# 1010829PA_HVFlyback_GD_Testboard_Flyback.net
KiCad netlist of a schematic drawn in Altium Designer
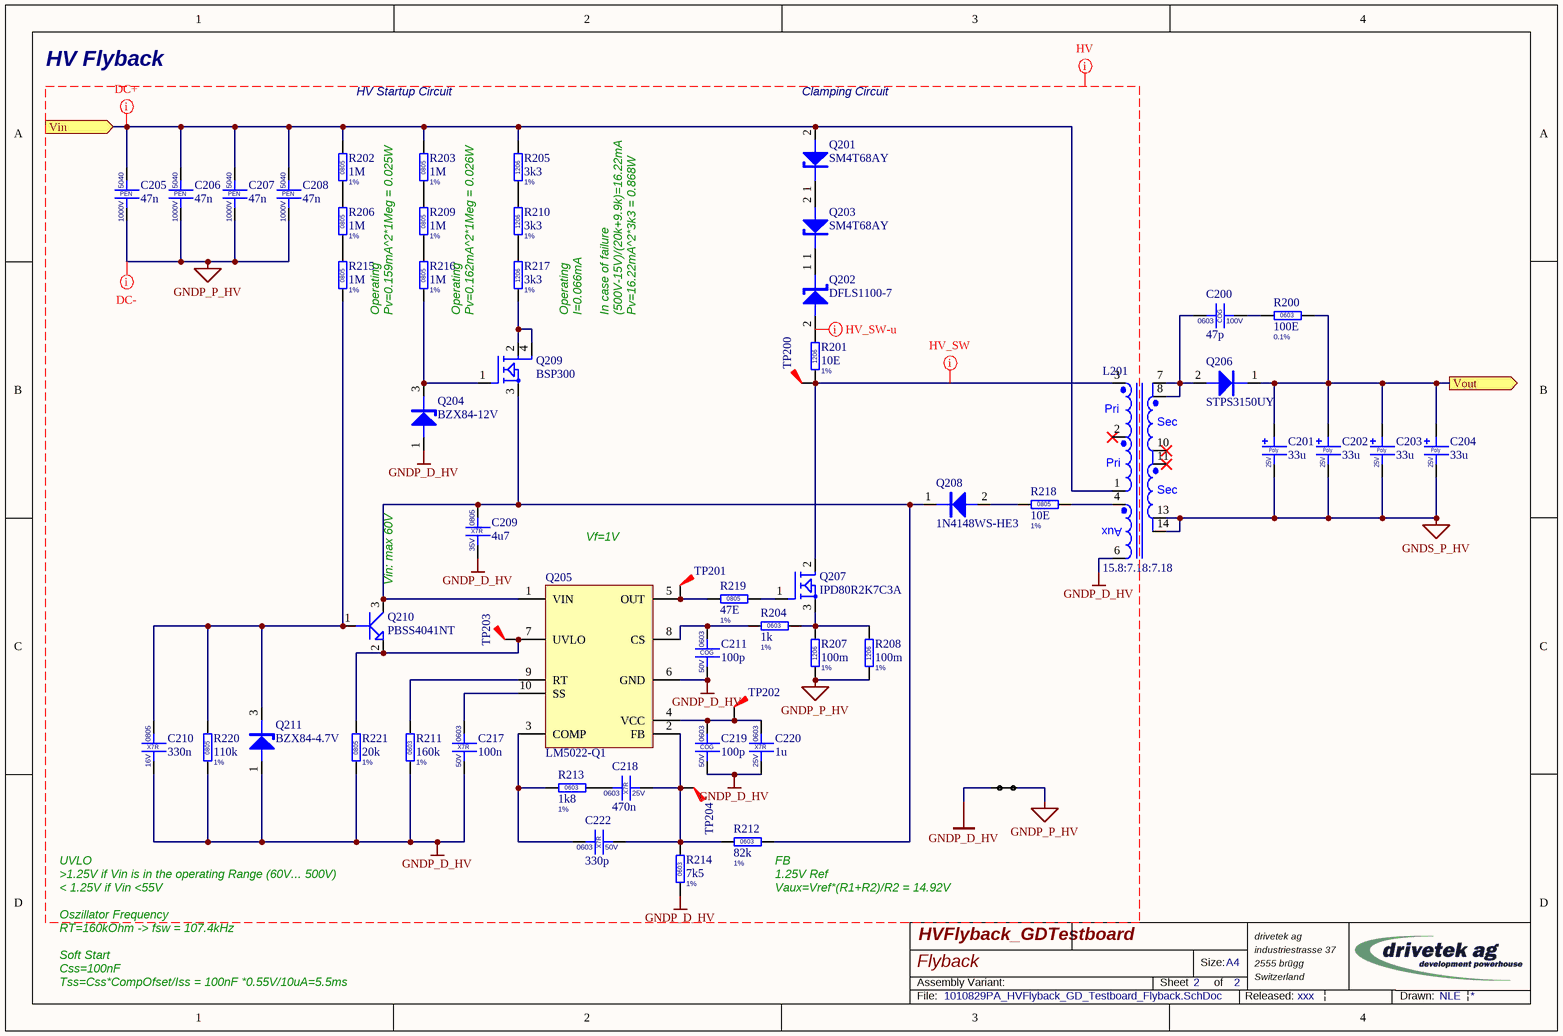
[diagram p0: 1010829PA_HVFlyback_GD_Testboard_Flyback.SchDoc]

(export (version "E")
  (design (tool "Eeschema 10.0.6"))
  (components
    (comp (ref "C200")
      (value "47p")
      (footprint "02_0603_DRK_1-7x1-0x0-9")
      (fields
        (field (name "CASENAME") "0603")
        (field (name "TYPE3") "COG")
        (field (name "VOLTAGE") "100V")
        (field (name "PART NUMBER") "02-0270")
        (field (name "TOLERANCE") "5")
        (field (name "AUTHOR") "RLE")
      )
      (libsource (lib "drivetek") (part "02_CAP"))
    )
    (comp (ref "C201")
      (value "33u")
      (footprint "02_ELKO-SMD-4x7-4_DRK_4-3x7-3x1-9")
      (fields
        (field (name "VOLTAGE") "25V")
        (field (name "TYPE2") "Poly")
        (field (name "PART NUMBER") "02-0399")
        (field (name "TOLERANCE") "20")
        (field (name "AUTHOR") "LME")
      )
      (libsource (lib "drivetek") (part "02_CAP-POL-P1-N2"))
    )
    (comp (ref "C202")
      (value "33u")
      (footprint "02_ELKO-SMD-4x7-4_DRK_4-3x7-3x1-9")
      (fields
        (field (name "VOLTAGE") "25V")
        (field (name "TYPE2") "Poly")
        (field (name "PART NUMBER") "02-0399")
        (field (name "TOLERANCE") "20")
        (field (name "AUTHOR") "LME")
      )
      (libsource (lib "drivetek") (part "02_CAP-POL-P1-N2"))
    )
    (comp (ref "C203")
      (value "33u")
      (footprint "02_ELKO-SMD-4x7-4_DRK_4-3x7-3x1-9")
      (fields
        (field (name "VOLTAGE") "25V")
        (field (name "TYPE2") "Poly")
        (field (name "PART NUMBER") "02-0399")
        (field (name "TOLERANCE") "20")
        (field (name "AUTHOR") "LME")
      )
      (libsource (lib "drivetek") (part "02_CAP-POL-P1-N2"))
    )
    (comp (ref "C204")
      (value "33u")
      (footprint "02_ELKO-SMD-4x7-4_DRK_4-3x7-3x1-9")
      (fields
        (field (name "VOLTAGE") "25V")
        (field (name "TYPE2") "Poly")
        (field (name "PART NUMBER") "02-0399")
        (field (name "TOLERANCE") "20")
        (field (name "AUTHOR") "LME")
      )
      (libsource (lib "drivetek") (part "02_CAP-POL-P1-N2"))
    )
    (comp (ref "C205")
      (value "47n")
      (footprint "02_5040_DRK_3-5mm")
      (fields
        (field (name "CASENAME") "5040")
        (field (name "TYPE3") "PEN")
        (field (name "VOLTAGE") "1000V")
        (field (name "PART NUMBER") "02-0364")
        (field (name "TOLERANCE") "10")
        (field (name "AUTHOR") "IKU")
      )
      (libsource (lib "drivetek") (part "02_CAP"))
    )
    (comp (ref "C206")
      (value "47n")
      (footprint "02_5040_DRK_3-5mm")
      (fields
        (field (name "CASENAME") "5040")
        (field (name "TYPE3") "PEN")
        (field (name "VOLTAGE") "1000V")
        (field (name "PART NUMBER") "02-0364")
        (field (name "TOLERANCE") "10")
        (field (name "AUTHOR") "IKU")
      )
      (libsource (lib "drivetek") (part "02_CAP"))
    )
    (comp (ref "C207")
      (value "47n")
      (footprint "02_5040_DRK_3-5mm")
      (fields
        (field (name "CASENAME") "5040")
        (field (name "TYPE3") "PEN")
        (field (name "VOLTAGE") "1000V")
        (field (name "PART NUMBER") "02-0364")
        (field (name "TOLERANCE") "10")
        (field (name "AUTHOR") "IKU")
      )
      (libsource (lib "drivetek") (part "02_CAP"))
    )
    (comp (ref "C208")
      (value "47n")
      (footprint "02_5040_DRK_3-5mm")
      (fields
        (field (name "CASENAME") "5040")
        (field (name "TYPE3") "PEN")
        (field (name "VOLTAGE") "1000V")
        (field (name "PART NUMBER") "02-0364")
        (field (name "TOLERANCE") "10")
        (field (name "AUTHOR") "IKU")
      )
      (libsource (lib "drivetek") (part "02_CAP"))
    )
    (comp (ref "C209")
      (value "4u7")
      (footprint "02_0805_DRK_2-2x1-5x1-3")
      (fields
        (field (name "CASENAME") "0805")
        (field (name "TYPE3") "X7R")
        (field (name "VOLTAGE") "35V")
        (field (name "PART NUMBER") "02-0353")
        (field (name "TOLERANCE") "10")
        (field (name "AUTHOR") "RLE")
      )
      (libsource (lib "drivetek") (part "02_CAP"))
    )
    (comp (ref "C210")
      (value "330n")
      (footprint "02_0805_DRK_2-2x1-5x1-3")
      (fields
        (field (name "CASENAME") "0805")
        (field (name "TYPE3") "X7R")
        (field (name "VOLTAGE") "16V")
        (field (name "PART NUMBER") "02-0058")
        (field (name "TOLERANCE") "10")
        (field (name "AUTHOR") "CBA")
        (field (name "CHECKED") "HHU")
      )
      (libsource (lib "drivetek") (part "02_CAP"))
    )
    (comp (ref "C211")
      (value "100p")
      (footprint "02_0603_DRK_1-7x1-0x0-9")
      (fields
        (field (name "CASENAME") "0603")
        (field (name "TYPE3") "COG")
        (field (name "VOLTAGE") "50V")
        (field (name "PART NUMBER") "02-0380")
        (field (name "TOLERANCE") "5")
        (field (name "AUTHOR") "RLE")
      )
      (libsource (lib "drivetek") (part "02_CAP"))
    )
    (comp (ref "C217")
      (value "100n")
      (footprint "02_0603_DRK_1-7x1-0x0-9")
      (fields
        (field (name "CASENAME") "0603")
        (field (name "TYPE3") "X7R")
        (field (name "VOLTAGE") "50V")
        (field (name "PART NUMBER") "02-0184")
        (field (name "TOLERANCE") "10")
        (field (name "AUTHOR") "MSC")
        (field (name "CHECKED") "HHU")
      )
      (libsource (lib "drivetek") (part "02_CAP"))
    )
    (comp (ref "C218")
      (value "470n")
      (footprint "02_0603_DRK_1-7x1-0x0-9")
      (fields
        (field (name "CASENAME") "0603")
        (field (name "TYPE3") "X7R")
        (field (name "VOLTAGE") "25V")
        (field (name "PART NUMBER") "02-0206")
        (field (name "TOLERANCE") "10")
        (field (name "AUTHOR") "RLE")
        (field (name "CHECKED") "CRA")
      )
      (libsource (lib "drivetek") (part "02_CAP"))
    )
    (comp (ref "C219")
      (value "100p")
      (footprint "02_0603_DRK_1-7x1-0x0-9")
      (fields
        (field (name "CASENAME") "0603")
        (field (name "TYPE3") "COG")
        (field (name "VOLTAGE") "50V")
        (field (name "PART NUMBER") "02-0380")
        (field (name "TOLERANCE") "5")
        (field (name "AUTHOR") "RLE")
      )
      (libsource (lib "drivetek") (part "02_CAP"))
    )
    (comp (ref "C220")
      (value "1u")
      (footprint "02_0603_DRK_1-7x1-0x0-9")
      (fields
        (field (name "CASENAME") "0603")
        (field (name "TYPE3") "X7R")
        (field (name "VOLTAGE") "25V")
        (field (name "PART NUMBER") "02-0275")
        (field (name "TOLERANCE") "10")
        (field (name "AUTHOR") "SSC")
      )
      (libsource (lib "drivetek") (part "02_CAP"))
    )
    (comp (ref "C222")
      (value "330p")
      (footprint "02_0603_DRK_1-7x1-0x0-9")
      (fields
        (field (name "CASENAME") "0603")
        (field (name "TYPE3") "X7R")
        (field (name "VOLTAGE") "50V")
        (field (name "PART NUMBER") "02-0026")
        (field (name "TOLERANCE") "10")
        (field (name "AUTHOR") "CBA")
        (field (name "CHECKED") "HHU")
      )
      (libsource (lib "drivetek") (part "02_CAP"))
    )
    (comp (ref "J200")
      (value "3x1top")
      (footprint "12_NetCon_top_3x1")
      (description "NetCon")
      (fields (field (name "PART NUMBER") "12-0017") (field (name "AUTHOR") "MSC"))
      (libsource (lib "drivetek") (part "12_NetCon"))
    )
    (comp (ref "L201")
      (value "15.8:7.18:7.18")
      (footprint "06_TRA_DRK_WUERTH-750871630")
      (description "Flyback Transformer on Würth 070-6258 Bobbin")
      (fields (field (name "PART NUMBER") "06-0145") (field (name "AUTHOR") "NLE"))
      (libsource (lib "drivetek") (part "06_TRA_DRK_WUERTH-750871630"))
    )
    (comp (ref "Q201")
      (value "SM4T68AY")
      (footprint "03_SMA_DRK")
      (fields
        (field (name "PART NUMBER") "03-0427")
        (field (name "VOLTAGE") "58V")
        (field (name "AUTHOR") "NLE")
      )
      (libsource (lib "drivetek") (part "03_ZDIODE_A2-K1"))
    )
    (comp (ref "Q202")
      (value "DFLS1100-7")
      (footprint "03_POWERDI_DRK")
      (fields
        (field (name "PART NUMBER") "03-0225")
        (field (name "VOLTAGE") "100V")
        (field (name "AUTHOR") "CSI")
      )
      (libsource (lib "drivetek") (part "03_SCHOTTKY_A2-K1"))
    )
    (comp (ref "Q203")
      (value "SM4T68AY")
      (footprint "03_SMA_DRK")
      (fields
        (field (name "PART NUMBER") "03-0427")
        (field (name "VOLTAGE") "58V")
        (field (name "AUTHOR") "NLE")
      )
      (libsource (lib "drivetek") (part "03_ZDIODE_A2-K1"))
    )
    (comp (ref "Q204")
      (value "BZX84-12V")
      (footprint "03_SOT23_DRK")
      (fields (field (name "PART NUMBER") "03-0210") (field (name "VOLTAGE") "12V"))
      (libsource (lib "drivetek") (part "03_ZDIODE_A1-K3"))
    )
    (comp (ref "Q205")
      (value "LM5022-Q1")
      (footprint "04_VSSOP-10_DRK")
      (fields (field (name "PART NUMBER") "04-0502") (field (name "AUTHOR") "LME"))
      (libsource (lib "drivetek") (part "04_SPREG_LM5022"))
    )
    (comp (ref "Q206")
      (value "STPS3150UY")
      (footprint "03_SMB_DRK")
      (fields
        (field (name "PART NUMBER") "03-0428")
        (field (name "VOLTAGE") "150V")
        (field (name "AUTHOR") "NLE")
      )
      (libsource (lib "drivetek") (part "03_DIODE_A2-K1"))
    )
    (comp (ref "Q207")
      (value "IPD80R2K7C3A")
      (footprint "03_PG-TO252-3-11")
      (fields
        (field (name "PART NUMBER") "03-0426")
        (field (name "VOLTAGE") "800V")
        (field (name "AUTHOR") "NLE")
      )
      (libsource (lib "drivetek") (part "03_NMOS_G1-D2-S3"))
    )
    (comp (ref "Q208")
      (value "1N4148WS-HE3")
      (footprint "03_SOD323_DRK")
      (fields
        (field (name "PART NUMBER") "03-0429")
        (field (name "VOLTAGE") "100V")
        (field (name "AUTHOR") "NLE")
      )
      (libsource (lib "drivetek") (part "03_DIODE_A2-K1"))
    )
    (comp (ref "Q209")
      (value "BSP300")
      (footprint "03_SOT-223_DRK")
      (fields
        (field (name "PART NUMBER") "03-0432")
        (field (name "VOLTAGE") "800V")
        (field (name "AUTHOR") "NLE")
      )
      (libsource (lib "drivetek") (part "03_NMOS_G1-D2-S3-D4"))
    )
    (comp (ref "Q210")
      (value "PBSS4041NT")
      (footprint "03_SOT23_DRK")
      (fields
        (field (name "PART NUMBER") "03-0198")
        (field (name "VOLTAGE") "60V")
        (field (name "AUTHOR") "SSC")
      )
      (libsource (lib "drivetek") (part "03_NPN_1B-2E-3C"))
    )
    (comp (ref "Q211")
      (value "BZX84-4.7V")
      (footprint "03_SOT23_DRK")
      (fields
        (field (name "PART NUMBER") "03-0027")
        (field (name "VOLTAGE") "4V7")
        (field (name "AUTHOR") "CBA")
      )
      (libsource (lib "drivetek") (part "03_ZDIODE_A1-K3"))
    )
    (comp (ref "R200")
      (value "100E")
      (footprint "01_0603_DRK_1-7x1-0x0-55")
      (fields
        (field (name "TOLERANCE") "0.1%")
        (field (name "CASENAME") "0603")
        (field (name "PART NUMBER") "01-0584")
        (field (name "VOLTAGE") "75V")
        (field (name "POWER") "100m")
        (field (name "AUTHOR") "MFR")
      )
      (libsource (lib "drivetek") (part "01_RES"))
    )
    (comp (ref "R201")
      (value "10E")
      (footprint "01_1206_DRK_3-4x1-8x0-65")
      (fields
        (field (name "TOLERANCE") "1%")
        (field (name "CASENAME") "1206")
        (field (name "PART NUMBER") "01-0261")
        (field (name "VOLTAGE") "200V")
        (field (name "POWER") "125m")
        (field (name "AUTHOR") "CBA")
        (field (name "CHECKED") "CBA")
      )
      (libsource (lib "drivetek") (part "01_RES"))
    )
    (comp (ref "R202")
      (value "1M")
      (footprint "01_0805_DRK_2-2x1-5x0-65")
      (fields
        (field (name "TOLERANCE") "1%")
        (field (name "CASENAME") "0805")
        (field (name "PART NUMBER") "01-0158")
        (field (name "VOLTAGE") "150V")
        (field (name "POWER") "100m")
        (field (name "AUTHOR") "CBA")
        (field (name "CHECKED") "CBA")
      )
      (libsource (lib "drivetek") (part "01_RES"))
    )
    (comp (ref "R203")
      (value "1M")
      (footprint "01_0805_DRK_2-2x1-5x0-65")
      (fields
        (field (name "TOLERANCE") "1%")
        (field (name "CASENAME") "0805")
        (field (name "PART NUMBER") "01-0158")
        (field (name "VOLTAGE") "150V")
        (field (name "POWER") "100m")
        (field (name "AUTHOR") "CBA")
        (field (name "CHECKED") "CBA")
      )
      (libsource (lib "drivetek") (part "01_RES"))
    )
    (comp (ref "R204")
      (value "1k")
      (footprint "01_0603_DRK_1-7x1-0x0-55")
      (fields
        (field (name "TOLERANCE") "1%")
        (field (name "CASENAME") "0603")
        (field (name "PART NUMBER") "01-0003")
        (field (name "VOLTAGE") "50V")
        (field (name "POWER") "63m")
        (field (name "AUTHOR") "CBA")
        (field (name "CHECKED") "CBA")
      )
      (libsource (lib "drivetek") (part "01_RES"))
    )
    (comp (ref "R205")
      (value "3k3")
      (footprint "01_1206_DRK_3-4x1-8x0-65")
      (fields
        (field (name "TOLERANCE") "1%")
        (field (name "CASENAME") "1206")
        (field (name "PART NUMBER") "01-0317")
        (field (name "VOLTAGE") "200V")
        (field (name "POWER") "125m")
        (field (name "AUTHOR") "CBA")
        (field (name "CHECKED") "CBA")
      )
      (libsource (lib "drivetek") (part "01_RES"))
    )
    (comp (ref "R206")
      (value "1M")
      (footprint "01_0805_DRK_2-2x1-5x0-65")
      (fields
        (field (name "TOLERANCE") "1%")
        (field (name "CASENAME") "0805")
        (field (name "PART NUMBER") "01-0158")
        (field (name "VOLTAGE") "150V")
        (field (name "POWER") "100m")
        (field (name "AUTHOR") "CBA")
        (field (name "CHECKED") "CBA")
      )
      (libsource (lib "drivetek") (part "01_RES"))
    )
    (comp (ref "R207")
      (value "100m")
      (footprint "01_1206_DRK_3-4x1-8x0-65")
      (fields
        (field (name "TOLERANCE") "1%")
        (field (name "CASENAME") "1206")
        (field (name "PART NUMBER") "01-0780")
        (field (name "VOLTAGE") "200V")
        (field (name "POWER") "500m")
        (field (name "AUTHOR") "LME")
      )
      (libsource (lib "drivetek") (part "01_RES"))
    )
    (comp (ref "R208")
      (value "100m")
      (footprint "01_1206_DRK_3-4x1-8x0-65")
      (fields
        (field (name "TOLERANCE") "1%")
        (field (name "CASENAME") "1206")
        (field (name "PART NUMBER") "01-0780")
        (field (name "VOLTAGE") "200V")
        (field (name "POWER") "500m")
        (field (name "AUTHOR") "LME")
      )
      (libsource (lib "drivetek") (part "01_RES"))
    )
    (comp (ref "R209")
      (value "1M")
      (footprint "01_0805_DRK_2-2x1-5x0-65")
      (fields
        (field (name "TOLERANCE") "1%")
        (field (name "CASENAME") "0805")
        (field (name "PART NUMBER") "01-0158")
        (field (name "VOLTAGE") "150V")
        (field (name "POWER") "100m")
        (field (name "AUTHOR") "CBA")
        (field (name "CHECKED") "CBA")
      )
      (libsource (lib "drivetek") (part "01_RES"))
    )
    (comp (ref "R210")
      (value "3k3")
      (footprint "01_1206_DRK_3-4x1-8x0-65")
      (fields
        (field (name "TOLERANCE") "1%")
        (field (name "CASENAME") "1206")
        (field (name "PART NUMBER") "01-0317")
        (field (name "VOLTAGE") "200V")
        (field (name "POWER") "125m")
        (field (name "AUTHOR") "CBA")
        (field (name "CHECKED") "CBA")
      )
      (libsource (lib "drivetek") (part "01_RES"))
    )
    (comp (ref "R211")
      (value "160k")
      (footprint "01_0603_DRK_1-7x1-0x0-55")
      (fields
        (field (name "TOLERANCE") "1%")
        (field (name "CASENAME") "0603")
        (field (name "PART NUMBER") "01-0032")
        (field (name "VOLTAGE") "50V")
        (field (name "POWER") "63m")
        (field (name "AUTHOR") "CBA")
        (field (name "CHECKED") "CBA")
      )
      (libsource (lib "drivetek") (part "01_RES"))
    )
    (comp (ref "R212")
      (value "82k")
      (footprint "01_0603_DRK_1-7x1-0x0-55")
      (fields
        (field (name "TOLERANCE") "1%")
        (field (name "CASENAME") "0603")
        (field (name "PART NUMBER") "01-0120")
        (field (name "VOLTAGE") "50V")
        (field (name "POWER") "63m")
        (field (name "AUTHOR") "CBA")
        (field (name "CHECKED") "CBA")
      )
      (libsource (lib "drivetek") (part "01_RES"))
    )
    (comp (ref "R213")
      (value "1k8")
      (footprint "01_0603_DRK_1-7x1-0x0-55")
      (fields
        (field (name "TOLERANCE") "1%")
        (field (name "CASENAME") "0603")
        (field (name "PART NUMBER") "01-0035")
        (field (name "VOLTAGE") "50V")
        (field (name "POWER") "63m")
        (field (name "AUTHOR") "CBA")
        (field (name "CHECKED") "CBA")
      )
      (libsource (lib "drivetek") (part "01_RES"))
    )
    (comp (ref "R214")
      (value "7k5")
      (footprint "01_0603_DRK_1-7x1-0x0-55")
      (fields
        (field (name "TOLERANCE") "1%")
        (field (name "CASENAME") "0603")
        (field (name "PART NUMBER") "01-0114")
        (field (name "VOLTAGE") "50V")
        (field (name "POWER") "63m")
        (field (name "AUTHOR") "CBA")
        (field (name "CHECKED") "CBA")
      )
      (libsource (lib "drivetek") (part "01_RES"))
    )
    (comp (ref "R215")
      (value "1M")
      (footprint "01_0805_DRK_2-2x1-5x0-65")
      (fields
        (field (name "TOLERANCE") "1%")
        (field (name "CASENAME") "0805")
        (field (name "PART NUMBER") "01-0158")
        (field (name "VOLTAGE") "150V")
        (field (name "POWER") "100m")
        (field (name "AUTHOR") "CBA")
        (field (name "CHECKED") "CBA")
      )
      (libsource (lib "drivetek") (part "01_RES"))
    )
    (comp (ref "R216")
      (value "1M")
      (footprint "01_0805_DRK_2-2x1-5x0-65")
      (fields
        (field (name "TOLERANCE") "1%")
        (field (name "CASENAME") "0805")
        (field (name "PART NUMBER") "01-0158")
        (field (name "VOLTAGE") "150V")
        (field (name "POWER") "100m")
        (field (name "AUTHOR") "CBA")
        (field (name "CHECKED") "CBA")
      )
      (libsource (lib "drivetek") (part "01_RES"))
    )
    (comp (ref "R217")
      (value "3k3")
      (footprint "01_1206_DRK_3-4x1-8x0-65")
      (fields
        (field (name "TOLERANCE") "1%")
        (field (name "CASENAME") "1206")
        (field (name "PART NUMBER") "01-0317")
        (field (name "VOLTAGE") "200V")
        (field (name "POWER") "125m")
        (field (name "AUTHOR") "CBA")
        (field (name "CHECKED") "CBA")
      )
      (libsource (lib "drivetek") (part "01_RES"))
    )
    (comp (ref "R218")
      (value "10E")
      (footprint "01_0805_DRK_2-2x1-5x0-65")
      (fields
        (field (name "TOLERANCE") "1%")
        (field (name "CASENAME") "0805")
        (field (name "PART NUMBER") "01-0159")
        (field (name "VOLTAGE") "150V")
        (field (name "POWER") "100m")
        (field (name "AUTHOR") "CBA")
        (field (name "CHECKED") "CBA")
      )
      (libsource (lib "drivetek") (part "01_RES"))
    )
    (comp (ref "R219")
      (value "47E")
      (footprint "01_0805_DRK_2-2x1-5x0-65")
      (fields
        (field (name "TOLERANCE") "1%")
        (field (name "CASENAME") "0805")
        (field (name "PART NUMBER") "01-0217")
        (field (name "VOLTAGE") "150V")
        (field (name "POWER") "100m")
        (field (name "AUTHOR") "CBA")
        (field (name "CHECKED") "CBA")
      )
      (libsource (lib "drivetek") (part "01_RES"))
    )
    (comp (ref "R220")
      (value "110k")
      (footprint "01_0805_DRK_2-2x1-5x0-65")
      (fields
        (field (name "TOLERANCE") "1%")
        (field (name "CASENAME") "0805")
        (field (name "PART NUMBER") "01-0163")
        (field (name "VOLTAGE") "150V")
        (field (name "POWER") "100m")
        (field (name "AUTHOR") "CBA")
        (field (name "CHECKED") "CBA")
      )
      (libsource (lib "drivetek") (part "01_RES"))
    )
    (comp (ref "R221")
      (value "20k")
      (footprint "01_0805_DRK_2-2x1-5x0-65")
      (fields
        (field (name "TOLERANCE") "1%")
        (field (name "CASENAME") "0805")
        (field (name "PART NUMBER") "01-0143")
        (field (name "VOLTAGE") "150V")
        (field (name "POWER") "100m")
        (field (name "AUTHOR") "CBA")
        (field (name "CHECKED") "CBA")
      )
      (libsource (lib "drivetek") (part "01_RES"))
    )
    (comp (ref "TP200")
      (value "TP SMD 1mm")
      (footprint "13_TP_1mm")
      (fields (field (name "PART NUMBER") "13-0304") (field (name "AUTHOR") "CSI"))
      (libsource (lib "drivetek") (part "13_TESTPOINT"))
    )
    (comp (ref "TP201")
      (value "TP SMD 1mm")
      (footprint "13_TP_1mm")
      (fields (field (name "PART NUMBER") "13-0304") (field (name "AUTHOR") "CSI"))
      (libsource (lib "drivetek") (part "13_TESTPOINT"))
    )
    (comp (ref "TP202")
      (value "TP SMD 1mm")
      (footprint "13_TP_1mm")
      (fields (field (name "PART NUMBER") "13-0304") (field (name "AUTHOR") "CSI"))
      (libsource (lib "drivetek") (part "13_TESTPOINT"))
    )
    (comp (ref "TP203")
      (value "TP SMD 1mm")
      (footprint "13_TP_1mm")
      (fields (field (name "PART NUMBER") "13-0304") (field (name "AUTHOR") "CSI"))
      (libsource (lib "drivetek") (part "13_TESTPOINT"))
    )
    (comp (ref "TP204")
      (value "TP SMD 1mm")
      (footprint "13_TP_1mm")
      (fields (field (name "PART NUMBER") "13-0304") (field (name "AUTHOR") "CSI"))
      (libsource (lib "drivetek") (part "13_TESTPOINT"))
    )
  )
  (nets
    (net (code "1") (name "/Vin") (class "Default")
      (node (ref "C205") (pin "1") (pintype "passive"))
      (node (ref "C206") (pin "1") (pintype "passive"))
      (node (ref "C207") (pin "1") (pintype "passive"))
      (node (ref "C208") (pin "1") (pintype "passive"))
      (node (ref "L201") (pin "1") (pinfunction "1_1") (pintype "passive"))
      (node (ref "Q201") (pin "2") (pintype "passive"))
      (node (ref "R202") (pin "2") (pintype "passive"))
      (node (ref "R203") (pin "2") (pintype "passive"))
      (node (ref "R205") (pin "2") (pintype "passive"))
    )
    (net (code "2") (name "/Vout") (class "Default")
      (node (ref "C201") (pin "1") (pintype "passive"))
      (node (ref "C202") (pin "1") (pintype "passive"))
      (node (ref "C203") (pin "1") (pintype "passive"))
      (node (ref "C204") (pin "1") (pintype "passive"))
      (node (ref "Q206") (pin "1") (pintype "passive"))
      (node (ref "R200") (pin "2") (pintype "passive"))
    )
    (net (code "3") (name "GNDP_D_HV") (class "Default")
      (node (ref "C209") (pin "2") (pintype "passive"))
      (node (ref "C210") (pin "2") (pintype "passive"))
      (node (ref "C211") (pin "2") (pintype "passive"))
      (node (ref "C217") (pin "2") (pintype "passive"))
      (node (ref "C219") (pin "2") (pintype "passive"))
      (node (ref "C220") (pin "2") (pintype "passive"))
      (node (ref "J200") (pin "1") (pinfunction "1_1") (pintype "passive"))
      (node (ref "L201") (pin "6") (pinfunction "6_6") (pintype "passive"))
      (node (ref "Q204") (pin "1") (pintype "passive"))
      (node (ref "Q205") (pin "6") (pinfunction "GND_6") (pintype "power_in"))
      (node (ref "Q211") (pin "1") (pintype "passive"))
      (node (ref "R211") (pin "1") (pintype "passive"))
      (node (ref "R214") (pin "1") (pintype "passive"))
      (node (ref "R220") (pin "1") (pintype "passive"))
      (node (ref "R221") (pin "1") (pintype "passive"))
    )
    (net (code "4") (name "GNDP_P_HV") (class "Default")
      (node (ref "C205") (pin "2") (pintype "passive"))
      (node (ref "C206") (pin "2") (pintype "passive"))
      (node (ref "C207") (pin "2") (pintype "passive"))
      (node (ref "C208") (pin "2") (pintype "passive"))
      (node (ref "J200") (pin "2") (pinfunction "2_2") (pintype "passive"))
      (node (ref "R207") (pin "1") (pintype "passive"))
      (node (ref "R208") (pin "1") (pintype "passive"))
    )
    (net (code "5") (name "GNDS_P_HV") (class "Default")
      (node (ref "C201") (pin "2") (pintype "passive"))
      (node (ref "C202") (pin "2") (pintype "passive"))
      (node (ref "C203") (pin "2") (pintype "passive"))
      (node (ref "C204") (pin "2") (pintype "passive"))
      (node (ref "L201") (pin "13") (pinfunction "13_13") (pintype "passive"))
      (node (ref "L201") (pin "14") (pinfunction "14_14") (pintype "passive"))
    )
    (net (code "6") (name "Net-(C200-Pad1)") (class "Default")
      (node (ref "C200") (pin "1") (pintype "passive"))
      (node (ref "L201") (pin "7") (pinfunction "7_7") (pintype "passive"))
      (node (ref "L201") (pin "8") (pinfunction "8_8") (pintype "passive"))
      (node (ref "Q206") (pin "2") (pintype "passive"))
    )
    (net (code "7") (name "Net-(C200-Pad2)") (class "Default")
      (node (ref "C200") (pin "2") (pintype "passive"))
      (node (ref "R200") (pin "1") (pintype "passive"))
    )
    (net (code "8") (name "Net-(C210-Pad1)") (class "Default")
      (node (ref "C210") (pin "1") (pintype "passive"))
      (node (ref "Q210") (pin "1") (pintype "passive"))
      (node (ref "Q211") (pin "3") (pintype "passive"))
      (node (ref "R215") (pin "1") (pintype "passive"))
      (node (ref "R220") (pin "2") (pintype "passive"))
    )
    (net (code "9") (name "Net-(C218-Pad1)") (class "Default")
      (node (ref "C218") (pin "1") (pintype "passive"))
      (node (ref "R213") (pin "2") (pintype "passive"))
    )
    (net (code "10") (name "Net-(L201-Pad3)") (class "Default")
      (node (ref "L201") (pin "3") (pinfunction "3_3") (pintype "passive"))
      (node (ref "Q207") (pin "2") (pintype "passive"))
      (node (ref "R201") (pin "2") (pintype "passive"))
      (node (ref "TP200") (pin "1") (pintype "passive"))
    )
    (net (code "11") (name "Net-(L201-Pad4)") (class "Default")
      (node (ref "L201") (pin "4") (pinfunction "4_4") (pintype "passive"))
      (node (ref "R218") (pin "2") (pintype "passive"))
    )
    (net (code "12") (name "Net-(Q201-Pad1)") (class "Default")
      (node (ref "Q201") (pin "1") (pintype "passive"))
      (node (ref "Q203") (pin "2") (pintype "passive"))
    )
    (net (code "13") (name "Net-(Q202-Pad1)") (class "Default")
      (node (ref "Q202") (pin "1") (pintype "passive"))
      (node (ref "Q203") (pin "1") (pintype "passive"))
    )
    (net (code "14") (name "Net-(Q202-Pad2)") (class "Default")
      (node (ref "Q202") (pin "2") (pintype "passive"))
      (node (ref "R201") (pin "1") (pintype "passive"))
    )
    (net (code "15") (name "Net-(Q204-Pad3)") (class "Default")
      (node (ref "Q204") (pin "3") (pintype "passive"))
      (node (ref "Q209") (pin "1") (pintype "passive"))
      (node (ref "R216") (pin "1") (pintype "passive"))
    )
    (net (code "16") (name "Net-(Q205-COMP)") (class "Default")
      (node (ref "C222") (pin "1") (pintype "passive"))
      (node (ref "Q205") (pin "3") (pinfunction "COMP_3") (pintype "passive"))
      (node (ref "R213") (pin "1") (pintype "passive"))
    )
    (net (code "17") (name "Net-(Q205-CS)") (class "Default")
      (node (ref "C211") (pin "1") (pintype "passive"))
      (node (ref "Q205") (pin "8") (pinfunction "CS_8") (pintype "passive"))
      (node (ref "R204") (pin "1") (pintype "passive"))
    )
    (net (code "18") (name "Net-(Q205-FB)") (class "Default")
      (node (ref "C218") (pin "2") (pintype "passive"))
      (node (ref "C222") (pin "2") (pintype "passive"))
      (node (ref "Q205") (pin "2") (pinfunction "FB_2") (pintype "passive"))
      (node (ref "R212") (pin "1") (pintype "passive"))
      (node (ref "R214") (pin "2") (pintype "passive"))
      (node (ref "TP204") (pin "1") (pintype "passive"))
    )
    (net (code "19") (name "Net-(Q205-OUT)") (class "Default")
      (node (ref "Q205") (pin "5") (pinfunction "OUT_5") (pintype "power_in"))
      (node (ref "R219") (pin "1") (pintype "passive"))
      (node (ref "TP201") (pin "1") (pintype "passive"))
    )
    (net (code "20") (name "Net-(Q205-RT)") (class "Default")
      (node (ref "Q205") (pin "9") (pinfunction "RT_9") (pintype "passive"))
      (node (ref "R211") (pin "2") (pintype "passive"))
    )
    (net (code "21") (name "Net-(Q205-SS)") (class "Default")
      (node (ref "C217") (pin "1") (pintype "passive"))
      (node (ref "Q205") (pin "10") (pinfunction "SS_10") (pintype "passive"))
    )
    (net (code "22") (name "Net-(Q205-UVLO)") (class "Default")
      (node (ref "Q205") (pin "7") (pinfunction "UVLO_7") (pintype "passive"))
      (node (ref "Q210") (pin "2") (pintype "passive"))
      (node (ref "R221") (pin "2") (pintype "passive"))
      (node (ref "TP203") (pin "1") (pintype "passive"))
    )
    (net (code "23") (name "Net-(Q205-VCC)") (class "Default")
      (node (ref "C219") (pin "1") (pintype "passive"))
      (node (ref "C220") (pin "1") (pintype "passive"))
      (node (ref "Q205") (pin "4") (pinfunction "VCC_4") (pintype "power_in"))
      (node (ref "TP202") (pin "1") (pintype "passive"))
    )
    (net (code "24") (name "Net-(Q205-VIN)") (class "Default")
      (node (ref "C209") (pin "1") (pintype "passive"))
      (node (ref "Q205") (pin "1") (pinfunction "VIN_1") (pintype "power_in"))
      (node (ref "Q208") (pin "1") (pintype "passive"))
      (node (ref "Q209") (pin "3") (pintype "passive"))
      (node (ref "Q210") (pin "3") (pintype "passive"))
      (node (ref "R212") (pin "2") (pintype "passive"))
    )
    (net (code "25") (name "Net-(Q207-Pad1)") (class "Default")
      (node (ref "Q207") (pin "1") (pintype "passive"))
      (node (ref "R219") (pin "2") (pintype "passive"))
    )
    (net (code "26") (name "Net-(Q207-Pad3)") (class "Default")
      (node (ref "Q207") (pin "3") (pintype "passive"))
      (node (ref "R204") (pin "2") (pintype "passive"))
      (node (ref "R207") (pin "2") (pintype "passive"))
      (node (ref "R208") (pin "2") (pintype "passive"))
    )
    (net (code "27") (name "Net-(Q208-Pad2)") (class "Default")
      (node (ref "Q208") (pin "2") (pintype "passive"))
      (node (ref "R218") (pin "1") (pintype "passive"))
    )
    (net (code "28") (name "Net-(Q209-Pad2)") (class "Default")
      (node (ref "Q209") (pin "2") (pintype "passive"))
      (node (ref "Q209") (pin "4") (pintype "passive"))
      (node (ref "R217") (pin "1") (pintype "passive"))
    )
    (net (code "29") (name "Net-(R202-Pad1)") (class "Default")
      (node (ref "R202") (pin "1") (pintype "passive"))
      (node (ref "R206") (pin "2") (pintype "passive"))
    )
    (net (code "30") (name "Net-(R203-Pad1)") (class "Default")
      (node (ref "R203") (pin "1") (pintype "passive"))
      (node (ref "R209") (pin "2") (pintype "passive"))
    )
    (net (code "31") (name "Net-(R205-Pad1)") (class "Default")
      (node (ref "R205") (pin "1") (pintype "passive"))
      (node (ref "R210") (pin "2") (pintype "passive"))
    )
    (net (code "32") (name "Net-(R206-Pad1)") (class "Default")
      (node (ref "R206") (pin "1") (pintype "passive"))
      (node (ref "R215") (pin "2") (pintype "passive"))
    )
    (net (code "33") (name "Net-(R209-Pad1)") (class "Default")
      (node (ref "R209") (pin "1") (pintype "passive"))
      (node (ref "R216") (pin "2") (pintype "passive"))
    )
    (net (code "34") (name "Net-(R210-Pad1)") (class "Default")
      (node (ref "R210") (pin "1") (pintype "passive"))
      (node (ref "R217") (pin "2") (pintype "passive"))
    )
    (net (code "35") (name "unconnected-(L201-7-Pad10)") (class "Default")
      (node (ref "L201") (pin "10") (pinfunction "7_10") (pintype "passive+no_connect"))
    )
    (net (code "36") (name "unconnected-(L201-Pad2)") (class "Default")
      (node (ref "L201") (pin "2") (pinfunction "2_2") (pintype "passive+no_connect"))
    )
    (net (code "37") (name "unconnected-(L201-Pad11)") (class "Default")
      (node (ref "L201") (pin "11") (pinfunction "11_11") (pintype "passive+no_connect"))
    )
  )
)
